# design.net
KiCad netlist of a schematic drawn in Altium Designer
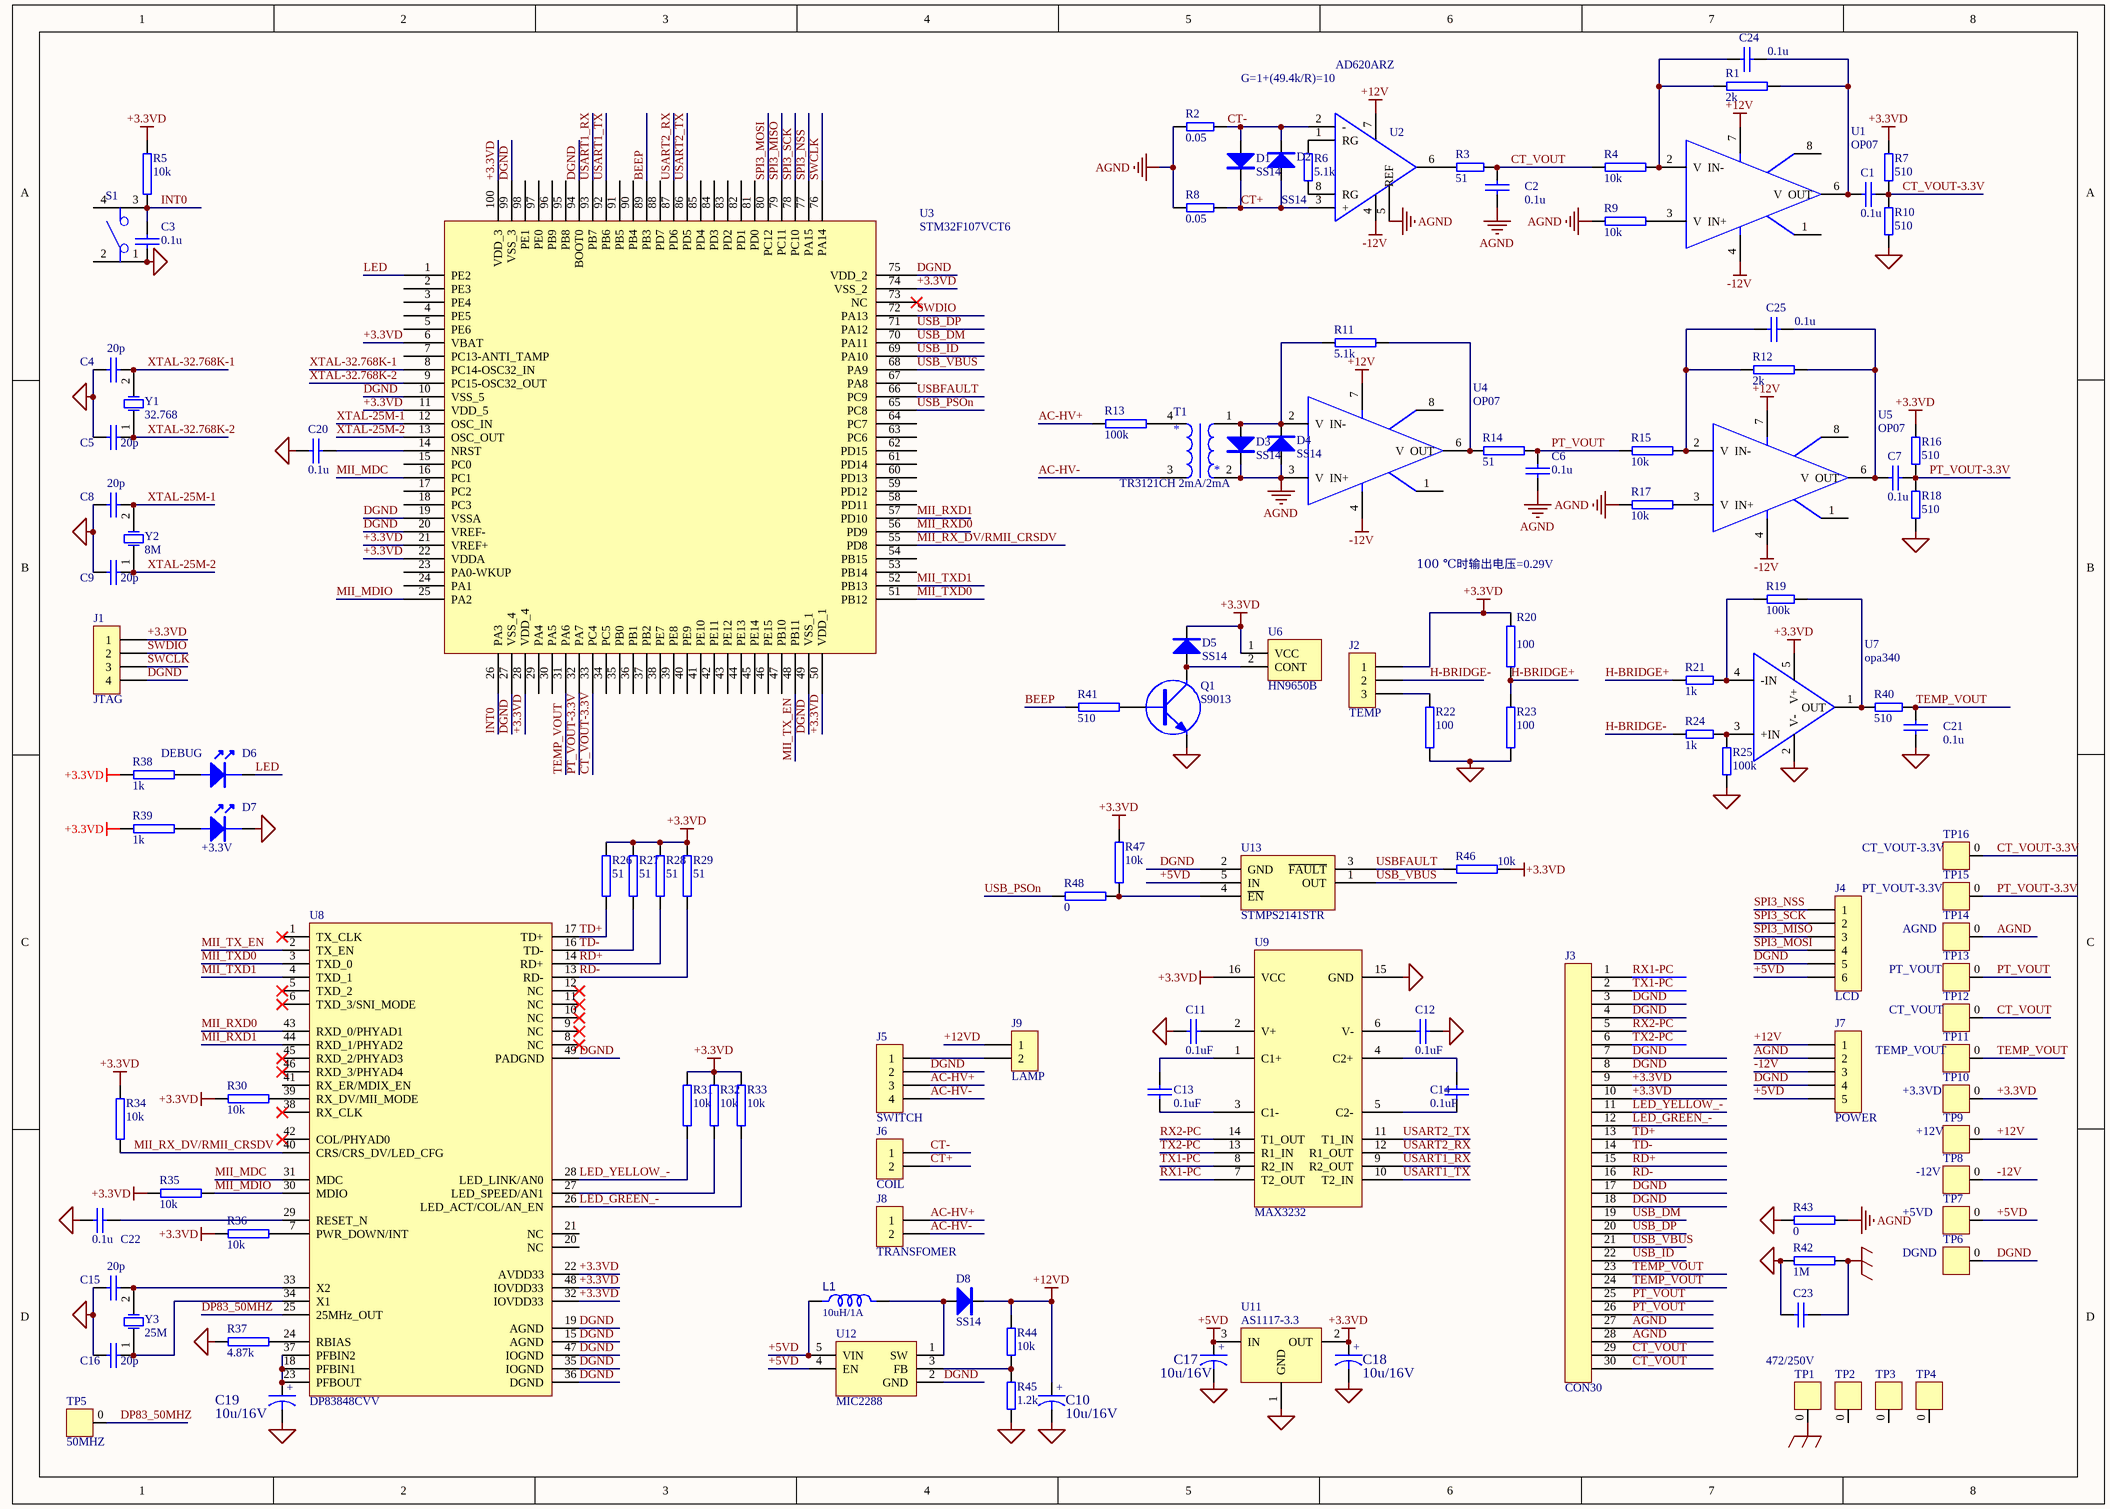
[diagram p0: 故指测试架主板.SchDoc]

(export (version "E")
  (design (tool "Eeschema 10.0.6"))
  (components
    (comp (ref "C1")
      (value "0.1u")
      (footprint "0805")
      (description "Capacitor")
      (libsource (lib "*") (part "CAP"))
    )
    (comp (ref "C2")
      (value "0.1u")
      (footprint "0805")
      (description "Capacitor")
      (libsource (lib "*") (part "CAP"))
    )
    (comp (ref "C3")
      (value "0.1u")
      (footprint "0805")
      (description "Capacitor")
      (libsource (lib "*") (part "CAP"))
    )
    (comp (ref "C4")
      (value "20p")
      (footprint "0805")
      (description "Capacitor")
      (libsource (lib "*") (part "CAP"))
    )
    (comp (ref "C5")
      (value "20p")
      (footprint "0805")
      (description "Capacitor")
      (libsource (lib "*") (part "CAP"))
    )
    (comp (ref "C6")
      (value "0.1u")
      (footprint "0805")
      (description "Capacitor")
      (libsource (lib "*") (part "CAP"))
    )
    (comp (ref "C7")
      (value "0.1u")
      (footprint "0805")
      (description "Capacitor")
      (libsource (lib "*") (part "CAP"))
    )
    (comp (ref "C8")
      (value "20p")
      (footprint "0805")
      (description "Capacitor")
      (libsource (lib "*") (part "CAP"))
    )
    (comp (ref "C9")
      (value "20p")
      (footprint "0805")
      (description "Capacitor")
      (libsource (lib "*") (part "CAP"))
    )
    (comp (ref "C10")
      (value "10u/16V")
      (footprint "1206C")
      (description "Capacitor")
      (libsource (lib "PCB_Project1") (part "CAPACITOR POL"))
    )
    (comp (ref "C11")
      (value "0.1uF")
      (footprint "0805")
      (description "Capacitor")
      (libsource (lib "*") (part "CAP"))
    )
    (comp (ref "C12")
      (value "0.1uF")
      (footprint "0805")
      (description "Capacitor")
      (libsource (lib "*") (part "CAP"))
    )
    (comp (ref "C13")
      (value "0.1uF")
      (footprint "0805")
      (description "Capacitor")
      (libsource (lib "*") (part "CAP"))
    )
    (comp (ref "C14")
      (value "0.1uF")
      (footprint "0805")
      (description "Capacitor")
      (libsource (lib "*") (part "CAP"))
    )
    (comp (ref "C15")
      (value "20p")
      (footprint "0805")
      (description "Capacitor")
      (libsource (lib "*") (part "CAP"))
    )
    (comp (ref "C16")
      (value "20p")
      (footprint "0805")
      (description "Capacitor")
      (libsource (lib "*") (part "CAP"))
    )
    (comp (ref "C17")
      (value "10u/16V")
      (footprint "1206C")
      (description "Capacitor")
      (libsource (lib "PCB_Project1") (part "CAPACITOR POL"))
    )
    (comp (ref "C18")
      (value "10u/16V")
      (footprint "1206C")
      (description "Capacitor")
      (libsource (lib "PCB_Project1") (part "CAPACITOR POL"))
    )
    (comp (ref "C19")
      (value "10u/16V")
      (footprint "1206C")
      (description "Capacitor")
      (libsource (lib "PCB_Project1") (part "CAPACITOR POL"))
    )
    (comp (ref "C20")
      (value "0.1u")
      (footprint "0805")
      (description "Capacitor")
      (libsource (lib "*") (part "CAP"))
    )
    (comp (ref "C21")
      (value "0.1u")
      (footprint "0805")
      (description "Capacitor")
      (libsource (lib "*") (part "CAP"))
    )
    (comp (ref "C22")
      (value "0.1u")
      (footprint "0805")
      (description "Capacitor")
      (libsource (lib "*") (part "CAP"))
    )
    (comp (ref "C23")
      (value "472/250V")
      (footprint "RAD0.3")
      (description "Capacitor")
      (libsource (lib "*") (part "CAP"))
    )
    (comp (ref "C24")
      (value "0.1u")
      (footprint "0805")
      (description "Capacitor")
      (libsource (lib "*") (part "CAP"))
    )
    (comp (ref "C25")
      (value "0.1u")
      (footprint "0805")
      (description "Capacitor")
      (libsource (lib "*") (part "CAP"))
    )
    (comp (ref "D1")
      (value "SS14")
      (footprint "SMA")
      (description "Diode")
      (libsource (lib "MPPT-LA") (part "SS14"))
    )
    (comp (ref "D2")
      (value "SS14")
      (footprint "SMA")
      (description "Diode")
      (libsource (lib "MPPT-LA") (part "SS14"))
    )
    (comp (ref "D3")
      (value "SS14")
      (footprint "SMA")
      (description "Diode")
      (libsource (lib "MPPT-LA") (part "SS14"))
    )
    (comp (ref "D4")
      (value "SS14")
      (footprint "SMA")
      (description "Diode")
      (libsource (lib "MPPT-LA") (part "SS14"))
    )
    (comp (ref "D5")
      (value "SS14")
      (footprint "SMA")
      (description "Diode")
      (libsource (lib "MPPT-LA") (part "SS14"))
    )
    (comp (ref "D6") (value "DEBUG") (footprint "LED-0805") (libsource (lib "MPPT-LA") (part "LED-0805")))
    (comp (ref "D7") (value "+3.3V") (footprint "LED-0805") (libsource (lib "MPPT-LA") (part "LED-0805")))
    (comp (ref "D8")
      (value "SS14")
      (footprint "SMA")
      (description "Diode")
      (libsource (lib "PCB_Project1") (part "SS14"))
    )
    (comp (ref "J1")
      (value "JTAG")
      (footprint "2510-4Y")
      (description "Connector")
      (libsource (lib "*") (part "CON4"))
    )
    (comp (ref "J2")
      (value "TEMP")
      (footprint "KF2EDG3.81-3P")
      (description "Connector")
      (libsource (lib "主板_1") (part "CON3"))
    )
    (comp (ref "J3") (value "CON30") (footprint "IDC-30") (libsource (lib "主板") (part "CON30")))
    (comp (ref "J4") (value "LCD") (footprint "2510-6Y") (libsource (lib "主板_1") (part "CON6")))
    (comp (ref "J5")
      (value "SWITCH")
      (footprint "KF2EDG3.81-4P")
      (description "Connector")
      (libsource (lib "测试架_1") (part "CON4"))
    )
    (comp (ref "J6")
      (value "COIL")
      (footprint "KF2EDG3.81-2P")
      (description "Connector")
      (libsource (lib "") (part "CON2_1"))
    )
    (comp (ref "J7") (value "POWER") (footprint "2510-5Y") (libsource (lib "LCD屏板_1") (part "CON5")))
    (comp (ref "J8")
      (value "TRANSFOMER")
      (footprint "KF2EDG3.81-2P")
      (description "Connector")
      (libsource (lib "") (part "CON2_1"))
    )
    (comp (ref "J9")
      (value "LAMP")
      (footprint "KF2EDG3.81-2P")
      (description "Connector")
      (libsource (lib "测试架_1") (part "CON2"))
    )
    (comp (ref "L1") (value "10uH/1A") (footprint "1206") (libsource (lib "*") (part "INDUCTOR_1")))
    (comp (ref "Q1") (value "S9013") (footprint "SOT-23") (libsource (lib "*") (part "S9013")))
    (comp (ref "R1") (value "2k") (footprint "0805") (libsource (lib "PCB_Project1") (part "R")))
    (comp (ref "R2") (value "0.05") (footprint "LVR03") (libsource (lib "芯片库") (part "电阻")))
    (comp (ref "R3") (value "51") (footprint "0805") (libsource (lib "芯片库") (part "电阻")))
    (comp (ref "R4") (value "10k") (footprint "0805") (libsource (lib "PCB_Project1") (part "R")))
    (comp (ref "R5") (value "10k") (footprint "0805") (libsource (lib "PCB_Project1") (part "R")))
    (comp (ref "R6") (value "5.1k") (footprint "0805") (libsource (lib "芯片库") (part "电阻")))
    (comp (ref "R7") (value "510") (footprint "0805") (libsource (lib "芯片库") (part "电阻")))
    (comp (ref "R8") (value "0.05") (footprint "LVR03") (libsource (lib "芯片库") (part "电阻")))
    (comp (ref "R9") (value "10k") (footprint "0805") (libsource (lib "PCB_Project1") (part "R")))
    (comp (ref "R10") (value "510") (footprint "0805") (libsource (lib "芯片库") (part "电阻")))
    (comp (ref "R11") (value "5.1k") (footprint "0805") (libsource (lib "PCB_Project1") (part "R")))
    (comp (ref "R12") (value "2k") (footprint "0805") (libsource (lib "PCB_Project1") (part "R")))
    (comp (ref "R13") (value "100k") (footprint "2512") (libsource (lib "PCB_Project1") (part "R")))
    (comp (ref "R14") (value "51") (footprint "0805") (libsource (lib "PCB_Project1") (part "R")))
    (comp (ref "R15") (value "10k") (footprint "0805") (libsource (lib "PCB_Project1") (part "R")))
    (comp (ref "R16") (value "510") (footprint "0805") (libsource (lib "芯片库") (part "电阻")))
    (comp (ref "R17") (value "10k") (footprint "0805") (libsource (lib "PCB_Project1") (part "R")))
    (comp (ref "R18") (value "510") (footprint "0805") (libsource (lib "芯片库") (part "电阻")))
    (comp (ref "R19") (value "100k") (footprint "0805") (libsource (lib "芯片库") (part "电阻")))
    (comp (ref "R20") (value "100") (footprint "0805") (libsource (lib "PCB_Project1") (part "R")))
    (comp (ref "R21") (value "1k") (footprint "0805") (libsource (lib "芯片库") (part "电阻")))
    (comp (ref "R22") (value "100") (footprint "0805") (libsource (lib "PCB_Project1") (part "R")))
    (comp (ref "R23") (value "100") (footprint "0805") (libsource (lib "PCB_Project1") (part "R")))
    (comp (ref "R24") (value "1k") (footprint "0805") (libsource (lib "芯片库") (part "电阻")))
    (comp (ref "R25") (value "100k") (footprint "0805") (libsource (lib "芯片库") (part "电阻")))
    (comp (ref "R26") (value "51") (footprint "0805") (libsource (lib "PCB_Project1") (part "R")))
    (comp (ref "R27") (value "51") (footprint "0805") (libsource (lib "PCB_Project1") (part "R")))
    (comp (ref "R28") (value "51") (footprint "0805") (libsource (lib "PCB_Project1") (part "R")))
    (comp (ref "R29") (value "51") (footprint "0805") (libsource (lib "PCB_Project1") (part "R")))
    (comp (ref "R30") (value "10k") (footprint "0805") (libsource (lib "PCB_Project1") (part "R")))
    (comp (ref "R31") (value "10k") (footprint "0805") (libsource (lib "PCB_Project1") (part "R")))
    (comp (ref "R32") (value "10k") (footprint "0805") (libsource (lib "PCB_Project1") (part "R")))
    (comp (ref "R33") (value "10k") (footprint "0805") (libsource (lib "PCB_Project1") (part "R")))
    (comp (ref "R34") (value "10k") (footprint "0805") (libsource (lib "PCB_Project1") (part "R")))
    (comp (ref "R35") (value "10k") (footprint "0805") (libsource (lib "PCB_Project1") (part "R")))
    (comp (ref "R36") (value "10k") (footprint "0805") (libsource (lib "PCB_Project1") (part "R")))
    (comp (ref "R37") (value "4.87k") (footprint "0805") (libsource (lib "PCB_Project1") (part "R")))
    (comp (ref "R38") (value "1k") (footprint "0805") (libsource (lib "PCB_Project1") (part "R")))
    (comp (ref "R39") (value "1k") (footprint "0805") (libsource (lib "PCB_Project1") (part "R")))
    (comp (ref "R40") (value "510") (footprint "0805") (libsource (lib "芯片库") (part "电阻")))
    (comp (ref "R41") (value "510") (footprint "0805") (libsource (lib "PCB_Project1") (part "R")))
    (comp (ref "R42") (value "1M") (footprint "0805") (libsource (lib "PCB_Project1") (part "R")))
    (comp (ref "R43") (value "0") (footprint "0805") (libsource (lib "PCB_Project1") (part "R")))
    (comp (ref "R44") (value "10k") (footprint "0805") (libsource (lib "芯片库") (part "电阻")))
    (comp (ref "R45") (value "1.2k") (footprint "0805") (libsource (lib "芯片库") (part "电阻")))
    (comp (ref "R46") (value "10k") (footprint "0805") (libsource (lib "PCB_Project1") (part "R")))
    (comp (ref "R47") (value "10k") (footprint "0805") (libsource (lib "PCB_Project1") (part "R")))
    (comp (ref "R48") (value "0") (footprint "0805") (libsource (lib "PCB_Project1") (part "R")))
    (comp (ref "S1") (value "~") (footprint "B3F-4055") (libsource (lib "*") (part "B3F-4055")))
    (comp (ref "T1")
      (value "TR3121CH 2mA/2mA")
      (footprint "TR3121CH")
      (libsource (lib "测试架_1") (part "TR3121CH 2mA/2mA"))
    )
    (comp (ref "TP1") (value "~") (footprint "PAD4.5") (libsource (lib "主板_1") (part "TESTPT")))
    (comp (ref "TP2") (value "~") (footprint "PAD4.5") (libsource (lib "主板_1") (part "TESTPT")))
    (comp (ref "TP3") (value "~") (footprint "PAD4.5") (libsource (lib "主板_1") (part "TESTPT")))
    (comp (ref "TP4") (value "~") (footprint "PAD4.5") (libsource (lib "主板_1") (part "TESTPT")))
    (comp (ref "TP5") (value "50MHZ") (footprint "TESTPOINT") (libsource (lib "") (part "TESTPT_1")))
    (comp (ref "TP6") (value "DGND") (footprint "TESTPOINT") (libsource (lib "") (part "TESTPT_1")))
    (comp (ref "TP7") (value "+5VD") (footprint "TESTPOINT") (libsource (lib "") (part "TESTPT_1")))
    (comp (ref "TP8") (value "-12V") (footprint "TESTPOINT") (libsource (lib "") (part "TESTPT_1")))
    (comp (ref "TP9") (value "+12V") (footprint "TESTPOINT") (libsource (lib "") (part "TESTPT_1")))
    (comp (ref "TP10") (value "+3.3VD") (footprint "TESTPOINT") (libsource (lib "") (part "TESTPT_1")))
    (comp (ref "TP11") (value "TEMP_VOUT") (footprint "TESTPOINT") (libsource (lib "") (part "TESTPT_1")))
    (comp (ref "TP12") (value "CT_VOUT") (footprint "TESTPOINT") (libsource (lib "") (part "TESTPT_1")))
    (comp (ref "TP13") (value "PT_VOUT") (footprint "TESTPOINT") (libsource (lib "") (part "TESTPT_1")))
    (comp (ref "TP14") (value "AGND") (footprint "TESTPOINT") (libsource (lib "") (part "TESTPT_1")))
    (comp (ref "TP15") (value "PT_VOUT-3.3V") (footprint "TESTPOINT") (libsource (lib "") (part "TESTPT_1")))
    (comp (ref "TP16") (value "CT_VOUT-3.3V") (footprint "TESTPOINT") (libsource (lib "") (part "TESTPT_1")))
    (comp (ref "U1")
      (value "OP07")
      (footprint "SO-8")
      (description "Ultra-Low Offset Voltage Operational Amplifier")
      (libsource (lib "主板") (part "OP07CS"))
    )
    (comp (ref "U2")
      (value "AD620ARZ")
      (footprint "SO-8")
      (description "Low-Cost, Low-Power Instrumentation Amplifier")
      (libsource (lib "PE-PA") (part "AD620AN"))
    )
    (comp (ref "U3")
      (value "STM32F107VCT6")
      (footprint "LQFP100_L")
      (libsource (lib "主板") (part "STM32F107VCT6"))
    )
    (comp (ref "U4")
      (value "OP07")
      (footprint "SO-8")
      (description "Ultra-Low Offset Voltage Operational Amplifier")
      (libsource (lib "主板") (part "OP07CS"))
    )
    (comp (ref "U5")
      (value "OP07")
      (footprint "SO-8")
      (description "Ultra-Low Offset Voltage Operational Amplifier")
      (libsource (lib "主板") (part "OP07CS"))
    )
    (comp (ref "U6") (value "HN9650B") (footprint "HN9650B") (libsource (lib "测试架_1") (part "HN9650B")))
    (comp (ref "U7") (value "opa340") (footprint "SOT23-5") (libsource (lib "测试架_1") (part "opa340")))
    (comp (ref "U8") (value "DP83848CVV") (footprint "DP83848") (libsource (lib "主板") (part "DP83848CVV")))
    (comp (ref "U9") (value "MAX3232") (footprint "SO-16") (libsource (lib "主板") (part "MAX3232")))
    (comp (ref "U11") (value "AS1117-3.3") (footprint "SOT-223") (libsource (lib "*") (part "AS1117-3.3")))
    (comp (ref "U12") (value "MIC2288") (footprint "SOT23-5") (libsource (lib "主板_1") (part "MIC2288")))
    (comp (ref "U13")
      (value "STMPS2141STR")
      (footprint "SOT23-5")
      (libsource (lib "主板") (part "STMPS2141STR"))
    )
    (comp (ref "Y1")
      (value "32.768")
      (footprint "XTAL-5032")
      (description "Crystal Oscillator")
      (fields (field (name "PUBLISHER") "Altium Limited"))
      (libsource (lib "haner") (part "XTAL"))
    )
    (comp (ref "Y2")
      (value "8M")
      (footprint "XTAL-5032")
      (description "Crystal Oscillator")
      (fields (field (name "PUBLISHER") "Altium Limited"))
      (libsource (lib "haner") (part "XTAL"))
    )
    (comp (ref "Y3")
      (value "25M")
      (footprint "XTAL-5032")
      (description "Crystal Oscillator")
      (fields (field (name "PUBLISHER") "Altium Limited"))
      (libsource (lib "haner") (part "XTAL"))
    )
  )
  (nets
    (net (code "1") (name "+3.3VD") (class "Default")
      (node (ref "C18") (pin "1") (pinfunction "1_1") (pintype "passive"))
      (node (ref "D5") (pin "2") (pinfunction "2_2") (pintype "passive"))
      (node (ref "J1") (pin "1") (pinfunction "1_1") (pintype "passive"))
      (node (ref "J2") (pin "1") (pinfunction "1_1") (pintype "passive"))
      (node (ref "J3") (pin "10") (pintype "passive"))
      (node (ref "J3") (pin "9") (pintype "passive"))
      (node (ref "R16") (pin "1") (pinfunction "1_1") (pintype "power_in"))
      (node (ref "R20") (pin "2") (pinfunction "2_2") (pintype "passive"))
      (node (ref "R26") (pin "2") (pinfunction "2_2") (pintype "passive"))
      (node (ref "R27") (pin "2") (pinfunction "2_2") (pintype "passive"))
      (node (ref "R28") (pin "2") (pinfunction "2_2") (pintype "passive"))
      (node (ref "R29") (pin "2") (pinfunction "2_2") (pintype "passive"))
      (node (ref "R30") (pin "1") (pinfunction "1_1") (pintype "passive"))
      (node (ref "R31") (pin "2") (pinfunction "2_2") (pintype "passive"))
      (node (ref "R32") (pin "2") (pinfunction "2_2") (pintype "passive"))
      (node (ref "R33") (pin "2") (pinfunction "2_2") (pintype "passive"))
      (node (ref "R34") (pin "1") (pinfunction "1_1") (pintype "passive"))
      (node (ref "R35") (pin "2") (pinfunction "2_2") (pintype "passive"))
      (node (ref "R36") (pin "1") (pinfunction "1_1") (pintype "passive"))
      (node (ref "R38") (pin "2") (pinfunction "2_2") (pintype "passive"))
      (node (ref "R39") (pin "2") (pinfunction "2_2") (pintype "passive"))
      (node (ref "R46") (pin "2") (pinfunction "2_2") (pintype "passive"))
      (node (ref "R47") (pin "1") (pinfunction "1_1") (pintype "passive"))
      (node (ref "R5") (pin "1") (pinfunction "1_1") (pintype "passive"))
      (node (ref "R7") (pin "1") (pinfunction "1_1") (pintype "power_in"))
      (node (ref "TP10") (pin "0") (pinfunction "0_0") (pintype "passive"))
      (node (ref "U11") (pin "2") (pinfunction "OUT_2") (pintype "passive"))
      (node (ref "U3") (pin "100") (pinfunction "VDD_3_100") (pintype "passive"))
      (node (ref "U3") (pin "11") (pinfunction "VDD_5_11") (pintype "passive"))
      (node (ref "U3") (pin "21") (pinfunction "VREF+_21") (pintype "passive"))
      (node (ref "U3") (pin "22") (pinfunction "VDDA_22") (pintype "passive"))
      (node (ref "U3") (pin "28") (pinfunction "VDD_4_28") (pintype "passive"))
      (node (ref "U3") (pin "50") (pinfunction "VDD_1_50") (pintype "passive"))
      (node (ref "U3") (pin "6") (pinfunction "VBAT_6") (pintype "passive"))
      (node (ref "U3") (pin "74") (pinfunction "VSS_2_74") (pintype "passive"))
      (node (ref "U6") (pin "1") (pinfunction "VCC_1") (pintype "passive"))
      (node (ref "U7") (pin "5") (pinfunction "V+_5") (pintype "passive"))
      (node (ref "U8") (pin "22") (pinfunction "AVDD33_22") (pintype "passive"))
      (node (ref "U8") (pin "32") (pinfunction "IOVDD33_32") (pintype "passive"))
      (node (ref "U8") (pin "48") (pinfunction "IOVDD33_48") (pintype "passive"))
      (node (ref "U9") (pin "16") (pinfunction "VCC_16") (pintype "power_in"))
    )
    (net (code "2") (name "+5VD") (class "Default")
      (node (ref "C17") (pin "1") (pinfunction "1_1") (pintype "passive"))
      (node (ref "J4") (pin "6") (pinfunction "6_6") (pintype "passive"))
      (node (ref "J7") (pin "5") (pinfunction "5_5") (pintype "passive"))
      (node (ref "L1") (pin "1") (pinfunction "1_1") (pintype "passive"))
      (node (ref "TP7") (pin "0") (pinfunction "0_0") (pintype "passive"))
      (node (ref "U11") (pin "3") (pinfunction "IN_3") (pintype "passive"))
      (node (ref "U12") (pin "4") (pinfunction "EN_4") (pintype "passive"))
      (node (ref "U12") (pin "5") (pinfunction "VIN_5") (pintype "passive"))
      (node (ref "U13") (pin "5") (pinfunction "IN_5") (pintype "passive"))
    )
    (net (code "3") (name "+12V") (class "Default")
      (node (ref "J7") (pin "1") (pinfunction "1_1") (pintype "passive"))
      (node (ref "TP9") (pin "0") (pinfunction "0_0") (pintype "passive"))
      (node (ref "U1") (pin "7") (pinfunction "VDD_7") (pintype "passive"))
      (node (ref "U2") (pin "7") (pinfunction "V+_7") (pintype "power_in"))
      (node (ref "U4") (pin "7") (pinfunction "VDD_7") (pintype "passive"))
      (node (ref "U5") (pin "7") (pinfunction "VDD_7") (pintype "passive"))
    )
    (net (code "4") (name "+12VD") (class "Default")
      (node (ref "C10") (pin "1") (pinfunction "1_1") (pintype "passive"))
      (node (ref "D8") (pin "2") (pinfunction "2_2") (pintype "passive"))
      (node (ref "J9") (pin "1") (pinfunction "1_1") (pintype "passive"))
      (node (ref "R44") (pin "1") (pinfunction "1_1") (pintype "power_in"))
    )
    (net (code "5") (name "-12V") (class "Default")
      (node (ref "J7") (pin "3") (pinfunction "3_3") (pintype "passive"))
      (node (ref "TP8") (pin "0") (pinfunction "0_0") (pintype "passive"))
      (node (ref "U1") (pin "4") (pinfunction "VSS_4") (pintype "passive"))
      (node (ref "U2") (pin "4") (pinfunction "V-_4") (pintype "power_in"))
      (node (ref "U4") (pin "4") (pinfunction "VSS_4") (pintype "passive"))
      (node (ref "U5") (pin "4") (pinfunction "VSS_4") (pintype "passive"))
    )
    (net (code "6") (name "/AC-HV+") (class "Default")
      (node (ref "J5") (pin "3") (pinfunction "3_3") (pintype "passive"))
      (node (ref "J8") (pin "1") (pinfunction "1_1") (pintype "passive"))
      (node (ref "R13") (pin "1") (pinfunction "1_1") (pintype "passive"))
    )
    (net (code "7") (name "/AC-HV-") (class "Default")
      (node (ref "J5") (pin "4") (pinfunction "4_4") (pintype "passive"))
      (node (ref "J8") (pin "2") (pinfunction "2_2") (pintype "passive"))
      (node (ref "T1") (pin "3") (pinfunction "3_3") (pintype "passive"))
    )
    (net (code "8") (name "/BEEP") (class "Default")
      (node (ref "R41") (pin "2") (pinfunction "2_2") (pintype "passive"))
      (node (ref "U3") (pin "89") (pinfunction "PB3_89") (pintype "passive"))
    )
    (net (code "9") (name "/CT+") (class "Default")
      (node (ref "D1") (pin "2") (pinfunction "2_2") (pintype "passive"))
      (node (ref "D2") (pin "1") (pinfunction "1_1") (pintype "passive"))
      (node (ref "J6") (pin "2") (pinfunction "2_2") (pintype "passive"))
      (node (ref "R8") (pin "1") (pinfunction "1_1") (pintype "power_in"))
      (node (ref "U2") (pin "3") (pinfunction "+_3") (pintype "passive"))
    )
    (net (code "10") (name "/CT-") (class "Default")
      (node (ref "D1") (pin "1") (pinfunction "1_1") (pintype "passive"))
      (node (ref "D2") (pin "2") (pinfunction "2_2") (pintype "passive"))
      (node (ref "J6") (pin "1") (pinfunction "1_1") (pintype "passive"))
      (node (ref "R2") (pin "1") (pinfunction "1_1") (pintype "power_in"))
      (node (ref "U2") (pin "2") (pinfunction "-_2") (pintype "passive"))
    )
    (net (code "11") (name "/CT_VOUT") (class "Default")
      (node (ref "C2") (pin "2") (pinfunction "2_2") (pintype "passive"))
      (node (ref "J3") (pin "29") (pinfunction "29_29") (pintype "passive"))
      (node (ref "J3") (pin "30") (pinfunction "30_30") (pintype "passive"))
      (node (ref "R3") (pin "1") (pinfunction "1_1") (pintype "power_in"))
      (node (ref "R4") (pin "1") (pinfunction "1_1") (pintype "passive"))
      (node (ref "TP12") (pin "0") (pinfunction "0_0") (pintype "passive"))
    )
    (net (code "12") (name "/CT_VOUT-3.3V") (class "Default")
      (node (ref "C1") (pin "1") (pinfunction "1_1") (pintype "passive"))
      (node (ref "R10") (pin "1") (pinfunction "1_1") (pintype "power_in"))
      (node (ref "R7") (pin "2") (pinfunction "2_2") (pintype "power_in"))
      (node (ref "TP16") (pin "0") (pinfunction "0_0") (pintype "passive"))
      (node (ref "U3") (pin "33") (pinfunction "PC4_33") (pintype "passive"))
    )
    (net (code "13") (name "/DP83_50MHZ") (class "Default")
      (node (ref "TP5") (pin "0") (pinfunction "0_0") (pintype "passive"))
      (node (ref "U8") (pin "25") (pinfunction "25MHz_OUT_25") (pintype "passive"))
    )
    (net (code "14") (name "/H-BRIDGE+") (class "Default")
      (node (ref "R20") (pin "1") (pinfunction "1_1") (pintype "passive"))
      (node (ref "R21") (pin "2") (pinfunction "2_2") (pintype "power_in"))
      (node (ref "R23") (pin "2") (pinfunction "2_2") (pintype "passive"))
    )
    (net (code "15") (name "/H-BRIDGE-") (class "Default")
      (node (ref "J2") (pin "2") (pinfunction "2_2") (pintype "passive"))
      (node (ref "R24") (pin "2") (pinfunction "2_2") (pintype "power_in"))
    )
    (net (code "16") (name "/INT0") (class "Default")
      (node (ref "C3") (pin "1") (pinfunction "1_1") (pintype "passive"))
      (node (ref "R5") (pin "2") (pinfunction "2_2") (pintype "passive"))
      (node (ref "S1") (pin "3") (pinfunction "3_3") (pintype "passive"))
      (node (ref "U3") (pin "26") (pinfunction "PA3_26") (pintype "passive"))
    )
    (net (code "17") (name "/LED") (class "Default")
      (node (ref "D6") (pin "2") (pinfunction "K_2") (pintype "passive"))
      (node (ref "U3") (pin "1") (pinfunction "PE2_1") (pintype "passive"))
    )
    (net (code "18") (name "/LED_GREEN_-") (class "Default")
      (node (ref "J3") (pin "12") (pintype "passive"))
      (node (ref "R33") (pin "1") (pinfunction "1_1") (pintype "passive"))
      (node (ref "U8") (pin "26") (pinfunction "LED_ACT/COL/AN_EN_26") (pintype "passive"))
    )
    (net (code "19") (name "/LED_YELLOW_-") (class "Default")
      (node (ref "J3") (pin "11") (pintype "passive"))
      (node (ref "R31") (pin "1") (pinfunction "1_1") (pintype "passive"))
      (node (ref "U8") (pin "28") (pinfunction "LED_LINK/AN0_28") (pintype "passive"))
    )
    (net (code "20") (name "/MII_MDC") (class "Default")
      (node (ref "U3") (pin "16") (pinfunction "PC1_16") (pintype "passive"))
      (node (ref "U8") (pin "31") (pinfunction "MDC_31") (pintype "passive"))
    )
    (net (code "21") (name "/MII_MDIO") (class "Default")
      (node (ref "R35") (pin "1") (pinfunction "1_1") (pintype "passive"))
      (node (ref "U3") (pin "25") (pinfunction "PA2_25") (pintype "passive"))
      (node (ref "U8") (pin "30") (pinfunction "MDIO_30") (pintype "passive"))
    )
    (net (code "22") (name "/MII_RXD0") (class "Default")
      (node (ref "U3") (pin "56") (pinfunction "PD9_56") (pintype "passive"))
      (node (ref "U8") (pin "43") (pinfunction "RXD_0/PHYAD1_43") (pintype "passive"))
    )
    (net (code "23") (name "/MII_RXD1") (class "Default")
      (node (ref "U3") (pin "57") (pinfunction "PD10_57") (pintype "passive"))
      (node (ref "U8") (pin "44") (pinfunction "RXD_1/PHYAD2_44") (pintype "passive"))
    )
    (net (code "24") (name "/MII_RX_DV{slash}RMII_CRSDV") (class "Default")
      (node (ref "R34") (pin "2") (pinfunction "2_2") (pintype "passive"))
      (node (ref "U3") (pin "55") (pinfunction "PD8_55") (pintype "passive"))
      (node (ref "U8") (pin "40") (pinfunction "CRS/CRS_DV/LED_CFG_40") (pintype "passive"))
    )
    (net (code "25") (name "/MII_TXD0") (class "Default")
      (node (ref "U3") (pin "51") (pinfunction "PB12_51") (pintype "passive"))
      (node (ref "U8") (pin "3") (pinfunction "TXD_0_3") (pintype "passive"))
    )
    (net (code "26") (name "/MII_TXD1") (class "Default")
      (node (ref "U3") (pin "52") (pinfunction "PB13_52") (pintype "passive"))
      (node (ref "U8") (pin "4") (pinfunction "TXD_1_4") (pintype "passive"))
    )
    (net (code "27") (name "/MII_TX_EN") (class "Default")
      (node (ref "U3") (pin "48") (pinfunction "PB11_48") (pintype "passive"))
      (node (ref "U8") (pin "2") (pinfunction "TX_EN_2") (pintype "passive"))
    )
    (net (code "28") (name "/PT_VOUT") (class "Default")
      (node (ref "C6") (pin "2") (pinfunction "2_2") (pintype "passive"))
      (node (ref "J3") (pin "25") (pinfunction "25_25") (pintype "passive"))
      (node (ref "J3") (pin "26") (pinfunction "26_26") (pintype "passive"))
      (node (ref "R14") (pin "2") (pinfunction "2_2") (pintype "passive"))
      (node (ref "R15") (pin "1") (pinfunction "1_1") (pintype "passive"))
      (node (ref "TP13") (pin "0") (pinfunction "0_0") (pintype "passive"))
    )
    (net (code "29") (name "/PT_VOUT-3.3V") (class "Default")
      (node (ref "C7") (pin "1") (pinfunction "1_1") (pintype "passive"))
      (node (ref "R16") (pin "2") (pinfunction "2_2") (pintype "power_in"))
      (node (ref "R18") (pin "1") (pinfunction "1_1") (pintype "power_in"))
      (node (ref "TP15") (pin "0") (pinfunction "0_0") (pintype "passive"))
      (node (ref "U3") (pin "32") (pinfunction "PA7_32") (pintype "passive"))
    )
    (net (code "30") (name "/RD+") (class "Default")
      (node (ref "J3") (pin "15") (pintype "passive"))
      (node (ref "R28") (pin "1") (pinfunction "1_1") (pintype "passive"))
      (node (ref "U8") (pin "14") (pinfunction "RD+_14") (pintype "passive"))
    )
    (net (code "31") (name "/RD-") (class "Default")
      (node (ref "J3") (pin "16") (pintype "passive"))
      (node (ref "R29") (pin "1") (pinfunction "1_1") (pintype "passive"))
      (node (ref "U8") (pin "13") (pinfunction "RD-_13") (pintype "passive"))
    )
    (net (code "32") (name "/RX1-PC") (class "Default")
      (node (ref "J3") (pin "1") (pintype "passive"))
      (node (ref "U9") (pin "7") (pinfunction "T2_OUT_7") (pintype "passive"))
    )
    (net (code "33") (name "/RX2-PC") (class "Default")
      (node (ref "J3") (pin "5") (pintype "passive"))
      (node (ref "U9") (pin "14") (pinfunction "T1_OUT_14") (pintype "passive"))
    )
    (net (code "34") (name "/SPI3_MISO") (class "Default")
      (node (ref "J4") (pin "3") (pinfunction "3_3") (pintype "passive"))
      (node (ref "U3") (pin "79") (pinfunction "PC11_79") (pintype "passive"))
    )
    (net (code "35") (name "/SPI3_MOSI") (class "Default")
      (node (ref "J4") (pin "4") (pinfunction "4_4") (pintype "passive"))
      (node (ref "U3") (pin "80") (pinfunction "PC12_80") (pintype "passive"))
    )
    (net (code "36") (name "/SPI3_NSS") (class "Default")
      (node (ref "J4") (pin "1") (pinfunction "1_1") (pintype "passive"))
      (node (ref "U3") (pin "77") (pinfunction "PA15_77") (pintype "passive"))
    )
    (net (code "37") (name "/SPI3_SCK") (class "Default")
      (node (ref "J4") (pin "2") (pinfunction "2_2") (pintype "passive"))
      (node (ref "U3") (pin "78") (pinfunction "PC10_78") (pintype "passive"))
    )
    (net (code "38") (name "/SWCLK") (class "Default")
      (node (ref "J1") (pin "3") (pinfunction "3_3") (pintype "passive"))
      (node (ref "U3") (pin "76") (pinfunction "PA14_76") (pintype "passive"))
    )
    (net (code "39") (name "/SWDIO") (class "Default")
      (node (ref "J1") (pin "2") (pinfunction "2_2") (pintype "passive"))
      (node (ref "U3") (pin "72") (pinfunction "PA13_72") (pintype "passive"))
    )
    (net (code "40") (name "/TD+") (class "Default")
      (node (ref "J3") (pin "13") (pintype "passive"))
      (node (ref "R26") (pin "1") (pinfunction "1_1") (pintype "passive"))
      (node (ref "U8") (pin "17") (pinfunction "TD+_17") (pintype "passive"))
    )
    (net (code "41") (name "/TD-") (class "Default")
      (node (ref "J3") (pin "14") (pintype "passive"))
      (node (ref "R27") (pin "1") (pinfunction "1_1") (pintype "passive"))
      (node (ref "U8") (pin "16") (pinfunction "TD-_16") (pintype "passive"))
    )
    (net (code "42") (name "/TEMP_VOUT") (class "Default")
      (node (ref "C21") (pin "2") (pinfunction "2_2") (pintype "passive"))
      (node (ref "J3") (pin "23") (pinfunction "23_23") (pintype "passive"))
      (node (ref "J3") (pin "24") (pinfunction "24_24") (pintype "passive"))
      (node (ref "R40") (pin "1") (pinfunction "1_1") (pintype "power_in"))
      (node (ref "TP11") (pin "0") (pinfunction "0_0") (pintype "passive"))
      (node (ref "U3") (pin "31") (pinfunction "PA6_31") (pintype "passive"))
    )
    (net (code "43") (name "/TX1-PC") (class "Default")
      (node (ref "J3") (pin "2") (pintype "passive"))
      (node (ref "U9") (pin "8") (pinfunction "R2_IN_8") (pintype "passive"))
    )
    (net (code "44") (name "/TX2-PC") (class "Default")
      (node (ref "J3") (pin "6") (pintype "passive"))
      (node (ref "U9") (pin "13") (pinfunction "R1_IN_13") (pintype "passive"))
    )
    (net (code "45") (name "/USART1_RX") (class "Default")
      (node (ref "U3") (pin "93") (pinfunction "PB7_93") (pintype "passive"))
      (node (ref "U9") (pin "9") (pinfunction "R2_OUT_9") (pintype "passive"))
    )
    (net (code "46") (name "/USART1_TX") (class "Default")
      (node (ref "U3") (pin "92") (pinfunction "PB6_92") (pintype "passive"))
      (node (ref "U9") (pin "10") (pinfunction "T2_IN_10") (pintype "passive"))
    )
    (net (code "47") (name "/USART2_RX") (class "Default")
      (node (ref "U3") (pin "87") (pinfunction "PD6_87") (pintype "passive"))
      (node (ref "U9") (pin "12") (pinfunction "R1_OUT_12") (pintype "passive"))
    )
    (net (code "48") (name "/USART2_TX") (class "Default")
      (node (ref "U3") (pin "86") (pinfunction "PD5_86") (pintype "passive"))
      (node (ref "U9") (pin "11") (pinfunction "T1_IN_11") (pintype "passive"))
    )
    (net (code "49") (name "/USBFAULT") (class "Default")
      (node (ref "R46") (pin "1") (pinfunction "1_1") (pintype "passive"))
      (node (ref "U13") (pin "3") (pinfunction "~{FAULT}_3") (pintype "passive"))
      (node (ref "U3") (pin "66") (pinfunction "PC9_66") (pintype "passive"))
    )
    (net (code "50") (name "/USB_DM") (class "Default")
      (node (ref "J3") (pin "19") (pintype "passive"))
      (node (ref "U3") (pin "70") (pinfunction "PA11_70") (pintype "passive"))
    )
    (net (code "51") (name "/USB_DP") (class "Default")
      (node (ref "J3") (pin "20") (pintype "passive"))
      (node (ref "U3") (pin "71") (pinfunction "PA12_71") (pintype "passive"))
    )
    (net (code "52") (name "/USB_ID") (class "Default")
      (node (ref "J3") (pin "22") (pinfunction "22_22") (pintype "passive"))
      (node (ref "U3") (pin "69") (pinfunction "PA10_69") (pintype "passive"))
    )
    (net (code "53") (name "/USB_PSOn") (class "Default")
      (node (ref "R48") (pin "1") (pinfunction "1_1") (pintype "passive"))
      (node (ref "U3") (pin "65") (pinfunction "PC8_65") (pintype "passive"))
    )
    (net (code "54") (name "/USB_VBUS") (class "Default")
      (node (ref "J3") (pin "21") (pinfunction "21_21") (pintype "passive"))
      (node (ref "U13") (pin "1") (pinfunction "OUT_1") (pintype "passive"))
      (node (ref "U3") (pin "68") (pinfunction "PA9_68") (pintype "passive"))
    )
    (net (code "55") (name "/XTAL-25M-1") (class "Default")
      (node (ref "C8") (pin "1") (pinfunction "1_1") (pintype "passive"))
      (node (ref "U3") (pin "12") (pinfunction "OSC_IN_12") (pintype "passive"))
      (node (ref "Y2") (pin "2") (pinfunction "OSC2_2") (pintype "passive"))
    )
    (net (code "56") (name "/XTAL-25M-2") (class "Default")
      (node (ref "C9") (pin "1") (pinfunction "1_1") (pintype "passive"))
      (node (ref "U3") (pin "13") (pinfunction "OSC_OUT_13") (pintype "passive"))
      (node (ref "Y2") (pin "1") (pinfunction "OSC1_1") (pintype "passive"))
    )
    (net (code "57") (name "/XTAL-32.768K-1") (class "Default")
      (node (ref "C4") (pin "1") (pinfunction "1_1") (pintype "passive"))
      (node (ref "U3") (pin "8") (pinfunction "PC14-OSC32_IN_8") (pintype "passive"))
      (node (ref "Y1") (pin "2") (pinfunction "OSC2_2") (pintype "passive"))
    )
    (net (code "58") (name "/XTAL-32.768K-2") (class "Default")
      (node (ref "C5") (pin "1") (pinfunction "1_1") (pintype "passive"))
      (node (ref "U3") (pin "9") (pinfunction "PC15-OSC32_OUT_9") (pintype "passive"))
      (node (ref "Y1") (pin "1") (pinfunction "OSC1_1") (pintype "passive"))
    )
    (net (code "59") (name "AGND") (class "Default")
      (node (ref "C2") (pin "1") (pinfunction "1_1") (pintype "passive"))
      (node (ref "C6") (pin "1") (pinfunction "1_1") (pintype "passive"))
      (node (ref "D3") (pin "2") (pinfunction "2_2") (pintype "passive"))
      (node (ref "D4") (pin "1") (pinfunction "1_1") (pintype "passive"))
      (node (ref "J3") (pin "27") (pinfunction "27_27") (pintype "passive"))
      (node (ref "J3") (pin "28") (pinfunction "28_28") (pintype "passive"))
      (node (ref "J7") (pin "2") (pinfunction "2_2") (pintype "passive"))
      (node (ref "R17") (pin "1") (pinfunction "1_1") (pintype "passive"))
      (node (ref "R2") (pin "2") (pinfunction "2_2") (pintype "power_in"))
      (node (ref "R43") (pin "1") (pinfunction "1_1") (pintype "passive"))
      (node (ref "R8") (pin "2") (pinfunction "2_2") (pintype "power_in"))
      (node (ref "R9") (pin "1") (pinfunction "1_1") (pintype "passive"))
      (node (ref "T1") (pin "2") (pinfunction "2_2") (pintype "passive"))
      (node (ref "TP14") (pin "0") (pinfunction "0_0") (pintype "passive"))
      (node (ref "U2") (pin "5") (pinfunction "REF_5") (pintype "passive"))
      (node (ref "U4") (pin "3") (pinfunction "V__IN+_3") (pintype "passive"))
    )
    (net (code "60") (name "DGND") (class "Default")
      (node (ref "C10") (pin "2") (pinfunction "2_2") (pintype "passive"))
      (node (ref "C11") (pin "2") (pinfunction "2_2") (pintype "passive"))
      (node (ref "C12") (pin "2") (pinfunction "2_2") (pintype "passive"))
      (node (ref "C15") (pin "2") (pinfunction "2_2") (pintype "passive"))
      (node (ref "C16") (pin "2") (pinfunction "2_2") (pintype "passive"))
      (node (ref "C17") (pin "2") (pinfunction "2_2") (pintype "passive"))
      (node (ref "C18") (pin "2") (pinfunction "2_2") (pintype "passive"))
      (node (ref "C19") (pin "2") (pinfunction "2_2") (pintype "passive"))
      (node (ref "C20") (pin "1") (pinfunction "1_1") (pintype "passive"))
      (node (ref "C21") (pin "1") (pinfunction "1_1") (pintype "passive"))
      (node (ref "C22") (pin "1") (pinfunction "1_1") (pintype "passive"))
      (node (ref "C23") (pin "2") (pinfunction "2_2") (pintype "passive"))
      (node (ref "C3") (pin "2") (pinfunction "2_2") (pintype "passive"))
      (node (ref "C4") (pin "2") (pinfunction "2_2") (pintype "passive"))
      (node (ref "C5") (pin "2") (pinfunction "2_2") (pintype "passive"))
      (node (ref "C8") (pin "2") (pinfunction "2_2") (pintype "passive"))
      (node (ref "C9") (pin "2") (pinfunction "2_2") (pintype "passive"))
      (node (ref "D7") (pin "2") (pinfunction "K_2") (pintype "passive"))
      (node (ref "J1") (pin "4") (pinfunction "4_4") (pintype "passive"))
      (node (ref "J3") (pin "17") (pintype "passive"))
      (node (ref "J3") (pin "18") (pintype "passive"))
      (node (ref "J3") (pin "3") (pintype "passive"))
      (node (ref "J3") (pin "4") (pintype "passive"))
      (node (ref "J3") (pin "7") (pintype "passive"))
      (node (ref "J3") (pin "8") (pintype "passive"))
      (node (ref "J4") (pin "5") (pinfunction "5_5") (pintype "passive"))
      (node (ref "J5") (pin "2") (pinfunction "2_2") (pintype "passive"))
      (node (ref "J7") (pin "4") (pinfunction "4_4") (pintype "passive"))
      (node (ref "Q1") (pin "2") (pinfunction "E_2") (pintype "passive"))
      (node (ref "R10") (pin "2") (pinfunction "2_2") (pintype "power_in"))
      (node (ref "R18") (pin "2") (pinfunction "2_2") (pintype "power_in"))
      (node (ref "R22") (pin "1") (pinfunction "1_1") (pintype "passive"))
      (node (ref "R23") (pin "1") (pinfunction "1_1") (pintype "passive"))
      (node (ref "R25") (pin "2") (pinfunction "2_2") (pintype "power_in"))
      (node (ref "R37") (pin "1") (pinfunction "1_1") (pintype "passive"))
      (node (ref "R42") (pin "2") (pinfunction "2_2") (pintype "passive"))
      (node (ref "R43") (pin "2") (pinfunction "2_2") (pintype "passive"))
      (node (ref "R45") (pin "2") (pinfunction "2_2") (pintype "power_in"))
      (node (ref "S1") (pin "1") (pinfunction "1_1") (pintype "passive"))
      (node (ref "TP6") (pin "0") (pinfunction "0_0") (pintype "passive"))
      (node (ref "U11") (pin "1") (pinfunction "GND_1") (pintype "passive"))
      (node (ref "U12") (pin "2") (pinfunction "GND_2") (pintype "passive"))
      (node (ref "U13") (pin "2") (pinfunction "GND_2") (pintype "passive"))
      (node (ref "U3") (pin "10") (pinfunction "VSS_5_10") (pintype "passive"))
      (node (ref "U3") (pin "19") (pinfunction "VSSA_19") (pintype "passive"))
      (node (ref "U3") (pin "20") (pinfunction "VREF-_20") (pintype "passive"))
      (node (ref "U3") (pin "27") (pinfunction "VSS_4_27") (pintype "passive"))
      (node (ref "U3") (pin "49") (pinfunction "VSS_1_49") (pintype "passive"))
      (node (ref "U3") (pin "75") (pinfunction "VDD_2_75") (pintype "passive"))
      (node (ref "U3") (pin "94") (pinfunction "BOOT0_94") (pintype "passive"))
      (node (ref "U3") (pin "99") (pinfunction "VSS_3_99") (pintype "passive"))
      (node (ref "U7") (pin "2") (pinfunction "V-_2") (pintype "passive"))
      (node (ref "U8") (pin "15") (pinfunction "AGND_15") (pintype "passive"))
      (node (ref "U8") (pin "19") (pinfunction "AGND_19") (pintype "passive"))
      (node (ref "U8") (pin "35") (pinfunction "IOGND_35") (pintype "passive"))
      (node (ref "U8") (pin "36") (pinfunction "DGND_36") (pintype "passive"))
      (node (ref "U8") (pin "47") (pinfunction "IOGND_47") (pintype "passive"))
      (node (ref "U8") (pin "49") (pinfunction "PADGND_49") (pintype "passive"))
      (node (ref "U9") (pin "15") (pinfunction "GND_15") (pintype "power_in"))
    )
    (net (code "61") (name "Net-(D6-A)") (class "Default")
      (node (ref "D6") (pin "1") (pinfunction "A_1") (pintype "passive"))
      (node (ref "R38") (pin "1") (pinfunction "1_1") (pintype "passive"))
    )
    (net (code "62") (name "Net-(D7-A)") (class "Default")
      (node (ref "D7") (pin "1") (pinfunction "A_1") (pintype "passive"))
      (node (ref "R39") (pin "1") (pinfunction "1_1") (pintype "passive"))
    )
    (net (code "63") (name "Net-(J2-Pad3)") (class "Default")
      (node (ref "J2") (pin "3") (pinfunction "3_3") (pintype "passive"))
      (node (ref "R22") (pin "2") (pinfunction "2_2") (pintype "passive"))
    )
    (net (code "64") (name "Net-(J5-Pad1)") (class "Default")
      (node (ref "J5") (pin "1") (pinfunction "1_1") (pintype "passive"))
      (node (ref "J9") (pin "2") (pinfunction "2_2") (pintype "passive"))
    )
    (net (code "65") (name "Net-(Q1-B)") (class "Default")
      (node (ref "Q1") (pin "1") (pinfunction "B_1") (pintype "passive"))
      (node (ref "R41") (pin "1") (pinfunction "1_1") (pintype "passive"))
    )
    (net (code "66") (name "Net-(Q1-C)") (class "Default")
      (node (ref "D5") (pin "1") (pinfunction "1_1") (pintype "passive"))
      (node (ref "Q1") (pin "3") (pinfunction "C_3") (pintype "passive"))
      (node (ref "U6") (pin "2") (pinfunction "CONT_2") (pintype "passive"))
    )
    (net (code "67") (name "Net-(R6-Pad1)") (class "Default")
      (node (ref "R6") (pin "1") (pinfunction "1_1") (pintype "power_in"))
      (node (ref "U2") (pin "8") (pinfunction "RG_8") (pintype "passive"))
    )
    (net (code "68") (name "Net-(R6-Pad2)") (class "Default")
      (node (ref "R6") (pin "2") (pinfunction "2_2") (pintype "power_in"))
      (node (ref "U2") (pin "1") (pinfunction "RG_1") (pintype "passive"))
    )
    (net (code "69") (name "Net-(R13-Pad2)") (class "Default")
      (node (ref "R13") (pin "2") (pinfunction "2_2") (pintype "passive"))
      (node (ref "T1") (pin "4") (pinfunction "4_4") (pintype "passive"))
    )
    (net (code "70") (name "Net-(U1-V__IN+)") (class "Default")
      (node (ref "R9") (pin "2") (pinfunction "2_2") (pintype "passive"))
      (node (ref "U1") (pin "3") (pinfunction "V__IN+_3") (pintype "passive"))
    )
    (net (code "71") (name "Net-(U1-V__IN-)") (class "Default")
      (node (ref "C24") (pin "2") (pinfunction "2_2") (pintype "passive"))
      (node (ref "R1") (pin "1") (pinfunction "1_1") (pintype "passive"))
      (node (ref "R4") (pin "2") (pinfunction "2_2") (pintype "passive"))
      (node (ref "U1") (pin "2") (pinfunction "V__IN-_2") (pintype "passive"))
    )
    (net (code "72") (name "Net-(U1-V__OUT)") (class "Default")
      (node (ref "C1") (pin "2") (pinfunction "2_2") (pintype "passive"))
      (node (ref "C24") (pin "1") (pinfunction "1_1") (pintype "passive"))
      (node (ref "R1") (pin "2") (pinfunction "2_2") (pintype "passive"))
      (node (ref "U1") (pin "6") (pinfunction "V__OUT_6") (pintype "passive"))
    )
    (net (code "73") (name "Net-(U2-OUT)") (class "Default")
      (node (ref "R3") (pin "2") (pinfunction "2_2") (pintype "power_in"))
      (node (ref "U2") (pin "6") (pinfunction "OUT_6") (pintype "passive"))
    )
    (net (code "74") (name "Net-(U3-NRST)") (class "Default")
      (node (ref "C20") (pin "2") (pinfunction "2_2") (pintype "passive"))
      (node (ref "U3") (pin "14") (pinfunction "NRST_14") (pintype "passive"))
    )
    (net (code "75") (name "Net-(U4-V__IN-)") (class "Default")
      (node (ref "D3") (pin "1") (pinfunction "1_1") (pintype "passive"))
      (node (ref "D4") (pin "2") (pinfunction "2_2") (pintype "passive"))
      (node (ref "R11") (pin "1") (pinfunction "1_1") (pintype "passive"))
      (node (ref "T1") (pin "1") (pinfunction "1_1") (pintype "passive"))
      (node (ref "U4") (pin "2") (pinfunction "V__IN-_2") (pintype "passive"))
    )
    (net (code "76") (name "Net-(U4-V__OUT)") (class "Default")
      (node (ref "R11") (pin "2") (pinfunction "2_2") (pintype "passive"))
      (node (ref "R14") (pin "1") (pinfunction "1_1") (pintype "passive"))
      (node (ref "U4") (pin "6") (pinfunction "V__OUT_6") (pintype "passive"))
    )
    (net (code "77") (name "Net-(U5-V__IN+)") (class "Default")
      (node (ref "R17") (pin "2") (pinfunction "2_2") (pintype "passive"))
      (node (ref "U5") (pin "3") (pinfunction "V__IN+_3") (pintype "passive"))
    )
    (net (code "78") (name "Net-(U5-V__IN-)") (class "Default")
      (node (ref "C25") (pin "2") (pinfunction "2_2") (pintype "passive"))
      (node (ref "R12") (pin "1") (pinfunction "1_1") (pintype "passive"))
      (node (ref "R15") (pin "2") (pinfunction "2_2") (pintype "passive"))
      (node (ref "U5") (pin "2") (pinfunction "V__IN-_2") (pintype "passive"))
    )
    (net (code "79") (name "Net-(U5-V__OUT)") (class "Default")
      (node (ref "C25") (pin "1") (pinfunction "1_1") (pintype "passive"))
      (node (ref "C7") (pin "2") (pinfunction "2_2") (pintype "passive"))
      (node (ref "R12") (pin "2") (pinfunction "2_2") (pintype "passive"))
      (node (ref "U5") (pin "6") (pinfunction "V__OUT_6") (pintype "passive"))
    )
    (net (code "80") (name "Net-(U7-+IN)") (class "Default")
      (node (ref "R24") (pin "1") (pinfunction "1_1") (pintype "power_in"))
      (node (ref "R25") (pin "1") (pinfunction "1_1") (pintype "power_in"))
      (node (ref "U7") (pin "3") (pinfunction "+IN_3") (pintype "passive"))
    )
    (net (code "81") (name "Net-(U7--IN)") (class "Default")
      (node (ref "R19") (pin "1") (pinfunction "1_1") (pintype "power_in"))
      (node (ref "R21") (pin "1") (pinfunction "1_1") (pintype "power_in"))
      (node (ref "U7") (pin "4") (pinfunction "-IN_4") (pintype "passive"))
    )
    (net (code "82") (name "Net-(U7-OUT)") (class "Default")
      (node (ref "R19") (pin "2") (pinfunction "2_2") (pintype "power_in"))
      (node (ref "R40") (pin "2") (pinfunction "2_2") (pintype "power_in"))
      (node (ref "U7") (pin "1") (pinfunction "OUT_1") (pintype "passive"))
    )
    (net (code "83") (name "Net-(U8-LED_SPEED{slash}AN1)") (class "Default")
      (node (ref "R32") (pin "1") (pinfunction "1_1") (pintype "passive"))
      (node (ref "U8") (pin "27") (pinfunction "LED_SPEED/AN1_27") (pintype "passive"))
    )
    (net (code "84") (name "Net-(U8-PFBIN1)") (class "Default")
      (node (ref "C19") (pin "1") (pinfunction "1_1") (pintype "passive"))
      (node (ref "U8") (pin "18") (pinfunction "PFBIN1_18") (pintype "passive"))
      (node (ref "U8") (pin "23") (pinfunction "PFBOUT_23") (pintype "passive"))
      (node (ref "U8") (pin "37") (pinfunction "PFBIN2_37") (pintype "passive"))
    )
    (net (code "85") (name "Net-(U8-PWR_DOWN{slash}INT)") (class "Default")
      (node (ref "R36") (pin "2") (pinfunction "2_2") (pintype "passive"))
      (node (ref "U8") (pin "7") (pinfunction "PWR_DOWN/INT_7") (pintype "passive"))
    )
    (net (code "86") (name "Net-(U8-RBIAS)") (class "Default")
      (node (ref "R37") (pin "2") (pinfunction "2_2") (pintype "passive"))
      (node (ref "U8") (pin "24") (pinfunction "RBIAS_24") (pintype "passive"))
    )
    (net (code "87") (name "Net-(U8-RESET_N)") (class "Default")
      (node (ref "C22") (pin "2") (pinfunction "2_2") (pintype "passive"))
      (node (ref "U8") (pin "29") (pinfunction "RESET_N_29") (pintype "passive"))
    )
    (net (code "88") (name "Net-(U8-RX_DV{slash}MII_MODE)") (class "Default")
      (node (ref "R30") (pin "2") (pinfunction "2_2") (pintype "passive"))
      (node (ref "U8") (pin "39") (pinfunction "RX_DV/MII_MODE_39") (pintype "passive"))
    )
    (net (code "89") (name "Net-(U8-X1)") (class "Default")
      (node (ref "C16") (pin "1") (pinfunction "1_1") (pintype "passive"))
      (node (ref "U8") (pin "34") (pinfunction "X1_34") (pintype "passive"))
      (node (ref "Y3") (pin "1") (pinfunction "OSC1_1") (pintype "passive"))
    )
    (net (code "90") (name "Net-(U8-X2)") (class "Default")
      (node (ref "C15") (pin "1") (pinfunction "1_1") (pintype "passive"))
      (node (ref "U8") (pin "33") (pinfunction "X2_33") (pintype "passive"))
      (node (ref "Y3") (pin "2") (pinfunction "OSC2_2") (pintype "passive"))
    )
    (net (code "91") (name "Net-(U9-C1+)") (class "Default")
      (node (ref "C13") (pin "1") (pinfunction "1_1") (pintype "passive"))
      (node (ref "U9") (pin "1") (pinfunction "C1+_1") (pintype "passive"))
    )
    (net (code "92") (name "Net-(U9-C1-)") (class "Default")
      (node (ref "C13") (pin "2") (pinfunction "2_2") (pintype "passive"))
      (node (ref "U9") (pin "3") (pinfunction "C1-_3") (pintype "passive"))
    )
    (net (code "93") (name "Net-(U9-C2+)") (class "Default")
      (node (ref "C14") (pin "1") (pinfunction "1_1") (pintype "passive"))
      (node (ref "U9") (pin "4") (pinfunction "C2+_4") (pintype "passive"))
    )
    (net (code "94") (name "Net-(U9-C2-)") (class "Default")
      (node (ref "C14") (pin "2") (pinfunction "2_2") (pintype "passive"))
      (node (ref "U9") (pin "5") (pinfunction "C2-_5") (pintype "passive"))
    )
    (net (code "95") (name "Net-(U9-V+)") (class "Default")
      (node (ref "C11") (pin "1") (pinfunction "1_1") (pintype "passive"))
      (node (ref "U9") (pin "2") (pinfunction "V+_2") (pintype "passive"))
    )
    (net (code "96") (name "Net-(U9-V-)") (class "Default")
      (node (ref "C12") (pin "1") (pinfunction "1_1") (pintype "passive"))
      (node (ref "U9") (pin "6") (pinfunction "V-_6") (pintype "passive"))
    )
    (net (code "97") (name "Net-(U12-FB)") (class "Default")
      (node (ref "R44") (pin "2") (pinfunction "2_2") (pintype "power_in"))
      (node (ref "R45") (pin "1") (pinfunction "1_1") (pintype "power_in"))
      (node (ref "U12") (pin "3") (pinfunction "FB_3") (pintype "passive"))
    )
    (net (code "98") (name "Net-(U12-SW)") (class "Default")
      (node (ref "D8") (pin "1") (pinfunction "1_1") (pintype "passive"))
      (node (ref "L1") (pin "2") (pinfunction "2_2") (pintype "passive"))
      (node (ref "U12") (pin "1") (pinfunction "SW_1") (pintype "passive"))
    )
    (net (code "99") (name "Net-(U13-~{EN})") (class "Default")
      (node (ref "R47") (pin "2") (pinfunction "2_2") (pintype "passive"))
      (node (ref "R48") (pin "2") (pinfunction "2_2") (pintype "passive"))
      (node (ref "U13") (pin "4") (pinfunction "~{EN}_4") (pintype "passive"))
    )
    (net (code "100") (name "PE") (class "Default")
      (node (ref "C23") (pin "1") (pinfunction "1_1") (pintype "passive"))
      (node (ref "R42") (pin "1") (pinfunction "1_1") (pintype "passive"))
      (node (ref "TP1") (pin "0") (pinfunction "0_0") (pintype "passive"))
    )
    (net (code "101") (name "unconnected-(S1-Pad2)") (class "Default")
      (node (ref "S1") (pin "2") (pinfunction "2_2") (pintype "passive"))
    )
    (net (code "102") (name "unconnected-(S1-Pad4)") (class "Default")
      (node (ref "S1") (pin "4") (pinfunction "4_4") (pintype "passive"))
    )
    (net (code "103") (name "unconnected-(TP2-Pad0)") (class "Default")
      (node (ref "TP2") (pin "0") (pinfunction "0_0") (pintype "passive"))
    )
    (net (code "104") (name "unconnected-(TP3-Pad0)") (class "Default")
      (node (ref "TP3") (pin "0") (pinfunction "0_0") (pintype "passive"))
    )
    (net (code "105") (name "unconnected-(TP4-Pad0)") (class "Default")
      (node (ref "TP4") (pin "0") (pinfunction "0_0") (pintype "passive"))
    )
    (net (code "106") (name "unconnected-(U1-VOSTRIM-Pad1)") (class "Default")
      (node (ref "U1") (pin "1") (pinfunction "VOSTRIM_1") (pintype "passive"))
    )
    (net (code "107") (name "unconnected-(U1-VOSTRIM-Pad8)") (class "Default")
      (node (ref "U1") (pin "8") (pinfunction "VOSTRIM_8") (pintype "passive"))
    )
    (net (code "108") (name "unconnected-(U3-NC-Pad73)") (class "Default")
      (node (ref "U3") (pin "73") (pinfunction "NC_73") (pintype "passive+no_connect"))
    )
    (net (code "109") (name "unconnected-(U3-PA0-WKUP-Pad23)") (class "Default")
      (node (ref "U3") (pin "23") (pinfunction "PA0-WKUP_23") (pintype "passive"))
    )
    (net (code "110") (name "unconnected-(U3-PA1-Pad24)") (class "Default")
      (node (ref "U3") (pin "24") (pinfunction "PA1_24") (pintype "passive"))
    )
    (net (code "111") (name "unconnected-(U3-PA4-Pad29)") (class "Default")
      (node (ref "U3") (pin "29") (pinfunction "PA4_29") (pintype "passive"))
    )
    (net (code "112") (name "unconnected-(U3-PA5-Pad30)") (class "Default")
      (node (ref "U3") (pin "30") (pinfunction "PA5_30") (pintype "passive"))
    )
    (net (code "113") (name "unconnected-(U3-PA8-Pad67)") (class "Default")
      (node (ref "U3") (pin "67") (pinfunction "PA8_67") (pintype "passive"))
    )
    (net (code "114") (name "unconnected-(U3-PB0-Pad35)") (class "Default")
      (node (ref "U3") (pin "35") (pinfunction "PB0_35") (pintype "passive"))
    )
    (net (code "115") (name "unconnected-(U3-PB1-Pad36)") (class "Default")
      (node (ref "U3") (pin "36") (pinfunction "PB1_36") (pintype "passive"))
    )
    (net (code "116") (name "unconnected-(U3-PB2-Pad37)") (class "Default")
      (node (ref "U3") (pin "37") (pinfunction "PB2_37") (pintype "passive"))
    )
    (net (code "117") (name "unconnected-(U3-PB4-Pad90)") (class "Default")
      (node (ref "U3") (pin "90") (pinfunction "PB4_90") (pintype "passive"))
    )
    (net (code "118") (name "unconnected-(U3-PB5-Pad91)") (class "Default")
      (node (ref "U3") (pin "91") (pinfunction "PB5_91") (pintype "passive"))
    )
    (net (code "119") (name "unconnected-(U3-PB8-Pad95)") (class "Default")
      (node (ref "U3") (pin "95") (pinfunction "PB8_95") (pintype "passive"))
    )
    (net (code "120") (name "unconnected-(U3-PB9-Pad96)") (class "Default")
      (node (ref "U3") (pin "96") (pinfunction "PB9_96") (pintype "passive"))
    )
    (net (code "121") (name "unconnected-(U3-PB10-Pad47)") (class "Default")
      (node (ref "U3") (pin "47") (pinfunction "PB10_47") (pintype "passive"))
    )
    (net (code "122") (name "unconnected-(U3-PB14-Pad53)") (class "Default")
      (node (ref "U3") (pin "53") (pinfunction "PB14_53") (pintype "passive"))
    )
    (net (code "123") (name "unconnected-(U3-PB15-Pad54)") (class "Default")
      (node (ref "U3") (pin "54") (pinfunction "PB15_54") (pintype "passive"))
    )
    (net (code "124") (name "unconnected-(U3-PC0-Pad15)") (class "Default")
      (node (ref "U3") (pin "15") (pinfunction "PC0_15") (pintype "passive"))
    )
    (net (code "125") (name "unconnected-(U3-PC2-Pad17)") (class "Default")
      (node (ref "U3") (pin "17") (pinfunction "PC2_17") (pintype "passive"))
    )
    (net (code "126") (name "unconnected-(U3-PC3-Pad18)") (class "Default")
      (node (ref "U3") (pin "18") (pinfunction "PC3_18") (pintype "passive"))
    )
    (net (code "127") (name "unconnected-(U3-PC5-Pad34)") (class "Default")
      (node (ref "U3") (pin "34") (pinfunction "PC5_34") (pintype "passive"))
    )
    (net (code "128") (name "unconnected-(U3-PC6-Pad63)") (class "Default")
      (node (ref "U3") (pin "63") (pinfunction "PC6_63") (pintype "passive"))
    )
    (net (code "129") (name "unconnected-(U3-PC7-Pad64)") (class "Default")
      (node (ref "U3") (pin "64") (pinfunction "PC7_64") (pintype "passive"))
    )
    (net (code "130") (name "unconnected-(U3-PC13-ANTI_TAMP-Pad7)") (class "Default")
      (node (ref "U3") (pin "7") (pinfunction "PC13-ANTI_TAMP_7") (pintype "passive"))
    )
    (net (code "131") (name "unconnected-(U3-PD0-Pad81)") (class "Default")
      (node (ref "U3") (pin "81") (pinfunction "PD0_81") (pintype "passive"))
    )
    (net (code "132") (name "unconnected-(U3-PD1-Pad82)") (class "Default")
      (node (ref "U3") (pin "82") (pinfunction "PD1_82") (pintype "passive"))
    )
    (net (code "133") (name "unconnected-(U3-PD2-Pad83)") (class "Default")
      (node (ref "U3") (pin "83") (pinfunction "PD2_83") (pintype "passive"))
    )
    (net (code "134") (name "unconnected-(U3-PD3-Pad84)") (class "Default")
      (node (ref "U3") (pin "84") (pinfunction "PD3_84") (pintype "passive"))
    )
    (net (code "135") (name "unconnected-(U3-PD4-Pad85)") (class "Default")
      (node (ref "U3") (pin "85") (pinfunction "PD4_85") (pintype "passive"))
    )
    (net (code "136") (name "unconnected-(U3-PD7-Pad88)") (class "Default")
      (node (ref "U3") (pin "88") (pinfunction "PD7_88") (pintype "passive"))
    )
    (net (code "137") (name "unconnected-(U3-PD11-Pad58)") (class "Default")
      (node (ref "U3") (pin "58") (pinfunction "PD11_58") (pintype "passive"))
    )
    (net (code "138") (name "unconnected-(U3-PD12-Pad59)") (class "Default")
      (node (ref "U3") (pin "59") (pinfunction "PD12_59") (pintype "passive"))
    )
    (net (code "139") (name "unconnected-(U3-PD13-Pad60)") (class "Default")
      (node (ref "U3") (pin "60") (pinfunction "PD13_60") (pintype "passive"))
    )
    (net (code "140") (name "unconnected-(U3-PD14-Pad61)") (class "Default")
      (node (ref "U3") (pin "61") (pinfunction "PD14_61") (pintype "passive"))
    )
    (net (code "141") (name "unconnected-(U3-PD15-Pad62)") (class "Default")
      (node (ref "U3") (pin "62") (pinfunction "PD15_62") (pintype "passive"))
    )
    (net (code "142") (name "unconnected-(U3-PE0-Pad97)") (class "Default")
      (node (ref "U3") (pin "97") (pinfunction "PE0_97") (pintype "passive"))
    )
    (net (code "143") (name "unconnected-(U3-PE1-Pad98)") (class "Default")
      (node (ref "U3") (pin "98") (pinfunction "PE1_98") (pintype "passive"))
    )
    (net (code "144") (name "unconnected-(U3-PE3-Pad2)") (class "Default")
      (node (ref "U3") (pin "2") (pinfunction "PE3_2") (pintype "passive"))
    )
    (net (code "145") (name "unconnected-(U3-PE4-Pad3)") (class "Default")
      (node (ref "U3") (pin "3") (pinfunction "PE4_3") (pintype "passive"))
    )
    (net (code "146") (name "unconnected-(U3-PE5-Pad4)") (class "Default")
      (node (ref "U3") (pin "4") (pinfunction "PE5_4") (pintype "passive"))
    )
    (net (code "147") (name "unconnected-(U3-PE6-Pad5)") (class "Default")
      (node (ref "U3") (pin "5") (pinfunction "PE6_5") (pintype "passive"))
    )
    (net (code "148") (name "unconnected-(U3-PE7-Pad38)") (class "Default")
      (node (ref "U3") (pin "38") (pinfunction "PE7_38") (pintype "passive"))
    )
    (net (code "149") (name "unconnected-(U3-PE8-Pad39)") (class "Default")
      (node (ref "U3") (pin "39") (pinfunction "PE8_39") (pintype "passive"))
    )
    (net (code "150") (name "unconnected-(U3-PE9-Pad40)") (class "Default")
      (node (ref "U3") (pin "40") (pinfunction "PE9_40") (pintype "passive"))
    )
    (net (code "151") (name "unconnected-(U3-PE10-Pad41)") (class "Default")
      (node (ref "U3") (pin "41") (pinfunction "PE10_41") (pintype "passive"))
    )
    (net (code "152") (name "unconnected-(U3-PE11-Pad42)") (class "Default")
      (node (ref "U3") (pin "42") (pinfunction "PE11_42") (pintype "passive"))
    )
    (net (code "153") (name "unconnected-(U3-PE12-Pad43)") (class "Default")
      (node (ref "U3") (pin "43") (pinfunction "PE12_43") (pintype "passive"))
    )
    (net (code "154") (name "unconnected-(U3-PE13-Pad44)") (class "Default")
      (node (ref "U3") (pin "44") (pinfunction "PE13_44") (pintype "passive"))
    )
    (net (code "155") (name "unconnected-(U3-PE14-Pad45)") (class "Default")
      (node (ref "U3") (pin "45") (pinfunction "PE14_45") (pintype "passive"))
    )
    (net (code "156") (name "unconnected-(U3-PE15-Pad46)") (class "Default")
      (node (ref "U3") (pin "46") (pinfunction "PE15_46") (pintype "passive"))
    )
    (net (code "157") (name "unconnected-(U4-VOSTRIM-Pad1)") (class "Default")
      (node (ref "U4") (pin "1") (pinfunction "VOSTRIM_1") (pintype "passive"))
    )
    (net (code "158") (name "unconnected-(U4-VOSTRIM-Pad8)") (class "Default")
      (node (ref "U4") (pin "8") (pinfunction "VOSTRIM_8") (pintype "passive"))
    )
    (net (code "159") (name "unconnected-(U5-VOSTRIM-Pad1)") (class "Default")
      (node (ref "U5") (pin "1") (pinfunction "VOSTRIM_1") (pintype "passive"))
    )
    (net (code "160") (name "unconnected-(U5-VOSTRIM-Pad8)") (class "Default")
      (node (ref "U5") (pin "8") (pinfunction "VOSTRIM_8") (pintype "passive"))
    )
    (net (code "161") (name "unconnected-(U8-COL{slash}PHYAD0-Pad42)") (class "Default")
      (node (ref "U8") (pin "42") (pinfunction "COL/PHYAD0_42") (pintype "passive+no_connect"))
    )
    (net (code "162") (name "unconnected-(U8-NC-Pad8)") (class "Default")
      (node (ref "U8") (pin "8") (pinfunction "NC_8") (pintype "passive+no_connect"))
    )
    (net (code "163") (name "unconnected-(U8-NC-Pad9)") (class "Default")
      (node (ref "U8") (pin "9") (pinfunction "NC_9") (pintype "passive+no_connect"))
    )
    (net (code "164") (name "unconnected-(U8-NC-Pad10)") (class "Default")
      (node (ref "U8") (pin "10") (pinfunction "NC_10") (pintype "passive+no_connect"))
    )
    (net (code "165") (name "unconnected-(U8-NC-Pad11)") (class "Default")
      (node (ref "U8") (pin "11") (pinfunction "NC_11") (pintype "passive+no_connect"))
    )
    (net (code "166") (name "unconnected-(U8-NC-Pad12)") (class "Default")
      (node (ref "U8") (pin "12") (pinfunction "NC_12") (pintype "passive+no_connect"))
    )
    (net (code "167") (name "unconnected-(U8-NC-Pad20)") (class "Default")
      (node (ref "U8") (pin "20") (pinfunction "NC_20") (pintype "passive"))
    )
    (net (code "168") (name "unconnected-(U8-NC-Pad21)") (class "Default")
      (node (ref "U8") (pin "21") (pinfunction "NC_21") (pintype "passive"))
    )
    (net (code "169") (name "unconnected-(U8-RXD_2{slash}PHYAD3-Pad45)") (class "Default")
      (node (ref "U8") (pin "45") (pinfunction "RXD_2/PHYAD3_45") (pintype "passive+no_connect"))
    )
    (net (code "170") (name "unconnected-(U8-RXD_3{slash}PHYAD4-Pad46)") (class "Default")
      (node (ref "U8") (pin "46") (pinfunction "RXD_3/PHYAD4_46") (pintype "passive+no_connect"))
    )
    (net (code "171") (name "unconnected-(U8-RX_CLK-Pad38)") (class "Default")
      (node (ref "U8") (pin "38") (pinfunction "RX_CLK_38") (pintype "passive+no_connect"))
    )
    (net (code "172") (name "unconnected-(U8-RX_ER{slash}MDIX_EN-Pad41)") (class "Default")
      (node (ref "U8") (pin "41") (pinfunction "RX_ER/MDIX_EN_41") (pintype "passive"))
    )
    (net (code "173") (name "unconnected-(U8-TXD_2-Pad5)") (class "Default")
      (node (ref "U8") (pin "5") (pinfunction "TXD_2_5") (pintype "passive+no_connect"))
    )
    (net (code "174") (name "unconnected-(U8-TXD_3{slash}SNI_MODE-Pad6)") (class "Default")
      (node (ref "U8") (pin "6") (pinfunction "TXD_3/SNI_MODE_6") (pintype "passive+no_connect"))
    )
    (net (code "175") (name "unconnected-(U8-TX_CLK-Pad1)") (class "Default")
      (node (ref "U8") (pin "1") (pinfunction "TX_CLK_1") (pintype "passive+no_connect"))
    )
  )
)
